# rgb.net
KiCad netlist of a schematic drawn in EAGLE
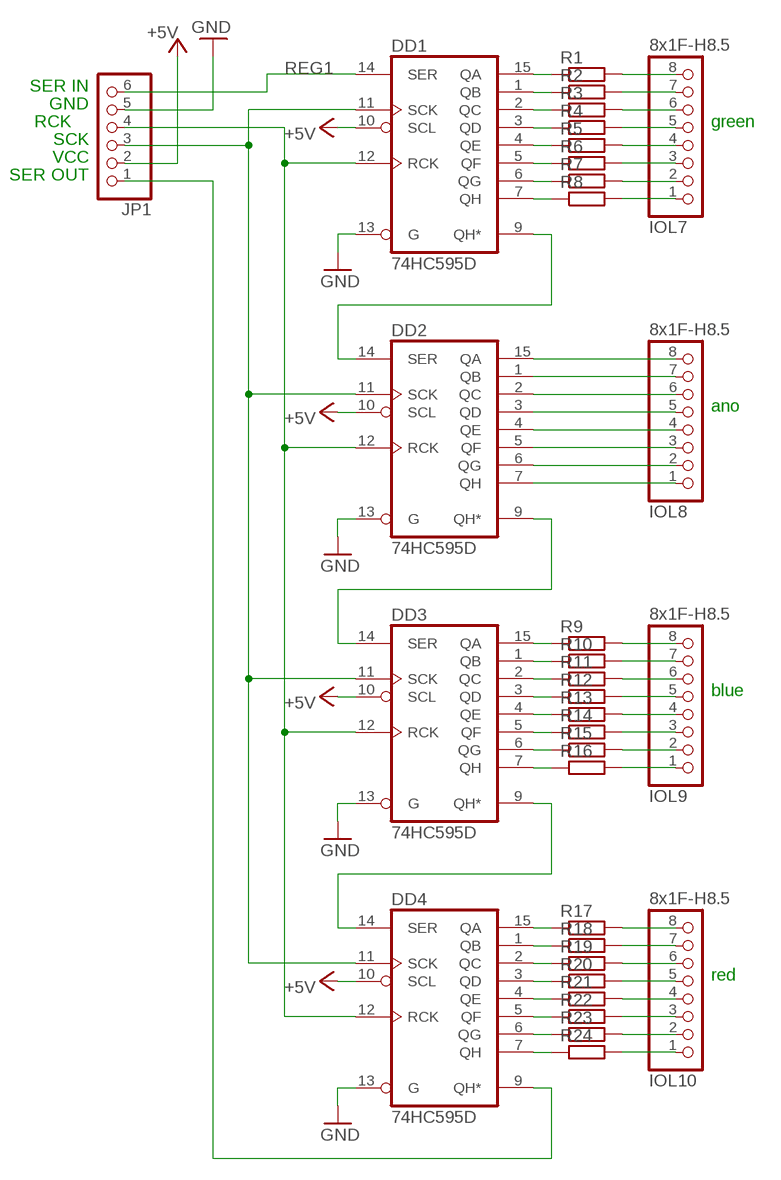
[diagram p0: schematic, sheet 1]

(export (version "E")
  (design (tool "Eeschema 10.0.6"))
  (components
    (comp (ref "DD1")
      (value "74HC595D")
      (footprint "eagle-import:SO16")
      (libsource (lib "eagle-import") (part "74595DHC"))
    )
    (comp (ref "DD2")
      (value "74HC595D")
      (footprint "eagle-import:SO16")
      (libsource (lib "eagle-import") (part "74595DHC"))
    )
    (comp (ref "DD3")
      (value "74HC595D")
      (footprint "eagle-import:SO16")
      (libsource (lib "eagle-import") (part "74595DHC"))
    )
    (comp (ref "DD4")
      (value "74HC595D")
      (footprint "eagle-import:SO16")
      (libsource (lib "eagle-import") (part "74595DHC"))
    )
    (comp (ref "IOL7")
      (value "8x1F-H8.5")
      (footprint "eagle-import:1X08")
      (libsource (lib "eagle-import") (part "PINHD-1X8"))
    )
    (comp (ref "IOL8")
      (value "8x1F-H8.5")
      (footprint "eagle-import:1X08")
      (libsource (lib "eagle-import") (part "PINHD-1X8"))
    )
    (comp (ref "IOL9")
      (value "8x1F-H8.5")
      (footprint "eagle-import:1X08")
      (libsource (lib "eagle-import") (part "PINHD-1X8"))
    )
    (comp (ref "IOL10")
      (value "8x1F-H8.5")
      (footprint "eagle-import:1X08")
      (libsource (lib "eagle-import") (part "PINHD-1X8"))
    )
    (comp (ref "JP1")
      (value "PINHD-1X6")
      (footprint "eagle-import:1X06")
      (libsource (lib "eagle-import") (part "PINHD-1X6"))
    )
    (comp (ref "R1")
      (value "R-EU_R0805")
      (footprint "eagle-import:R0805")
      (libsource (lib "eagle-import") (part "R-EU_R0805"))
    )
    (comp (ref "R2")
      (value "R-EU_R0805")
      (footprint "eagle-import:R0805")
      (libsource (lib "eagle-import") (part "R-EU_R0805"))
    )
    (comp (ref "R3")
      (value "R-EU_R0805")
      (footprint "eagle-import:R0805")
      (libsource (lib "eagle-import") (part "R-EU_R0805"))
    )
    (comp (ref "R4")
      (value "R-EU_R0805")
      (footprint "eagle-import:R0805")
      (libsource (lib "eagle-import") (part "R-EU_R0805"))
    )
    (comp (ref "R5")
      (value "R-EU_R0805")
      (footprint "eagle-import:R0805")
      (libsource (lib "eagle-import") (part "R-EU_R0805"))
    )
    (comp (ref "R6")
      (value "R-EU_R0805")
      (footprint "eagle-import:R0805")
      (libsource (lib "eagle-import") (part "R-EU_R0805"))
    )
    (comp (ref "R7")
      (value "R-EU_R0805")
      (footprint "eagle-import:R0805")
      (libsource (lib "eagle-import") (part "R-EU_R0805"))
    )
    (comp (ref "R8")
      (value "R-EU_R0805")
      (footprint "eagle-import:R0805")
      (libsource (lib "eagle-import") (part "R-EU_R0805"))
    )
    (comp (ref "R9")
      (value "R-EU_R0805")
      (footprint "eagle-import:R0805")
      (libsource (lib "eagle-import") (part "R-EU_R0805"))
    )
    (comp (ref "R10")
      (value "R-EU_R0805")
      (footprint "eagle-import:R0805")
      (libsource (lib "eagle-import") (part "R-EU_R0805"))
    )
    (comp (ref "R11")
      (value "R-EU_R0805")
      (footprint "eagle-import:R0805")
      (libsource (lib "eagle-import") (part "R-EU_R0805"))
    )
    (comp (ref "R12")
      (value "R-EU_R0805")
      (footprint "eagle-import:R0805")
      (libsource (lib "eagle-import") (part "R-EU_R0805"))
    )
    (comp (ref "R13")
      (value "R-EU_R0805")
      (footprint "eagle-import:R0805")
      (libsource (lib "eagle-import") (part "R-EU_R0805"))
    )
    (comp (ref "R14")
      (value "R-EU_R0805")
      (footprint "eagle-import:R0805")
      (libsource (lib "eagle-import") (part "R-EU_R0805"))
    )
    (comp (ref "R15")
      (value "R-EU_R0805")
      (footprint "eagle-import:R0805")
      (libsource (lib "eagle-import") (part "R-EU_R0805"))
    )
    (comp (ref "R16")
      (value "R-EU_R0805")
      (footprint "eagle-import:R0805")
      (libsource (lib "eagle-import") (part "R-EU_R0805"))
    )
    (comp (ref "R17")
      (value "R-EU_R0805")
      (footprint "eagle-import:R0805")
      (libsource (lib "eagle-import") (part "R-EU_R0805"))
    )
    (comp (ref "R18")
      (value "R-EU_R0805")
      (footprint "eagle-import:R0805")
      (libsource (lib "eagle-import") (part "R-EU_R0805"))
    )
    (comp (ref "R19")
      (value "R-EU_R0805")
      (footprint "eagle-import:R0805")
      (libsource (lib "eagle-import") (part "R-EU_R0805"))
    )
    (comp (ref "R20")
      (value "R-EU_R0805")
      (footprint "eagle-import:R0805")
      (libsource (lib "eagle-import") (part "R-EU_R0805"))
    )
    (comp (ref "R21")
      (value "R-EU_R0805")
      (footprint "eagle-import:R0805")
      (libsource (lib "eagle-import") (part "R-EU_R0805"))
    )
    (comp (ref "R22")
      (value "R-EU_R0805")
      (footprint "eagle-import:R0805")
      (libsource (lib "eagle-import") (part "R-EU_R0805"))
    )
    (comp (ref "R23")
      (value "R-EU_R0805")
      (footprint "eagle-import:R0805")
      (libsource (lib "eagle-import") (part "R-EU_R0805"))
    )
    (comp (ref "R24")
      (value "R-EU_R0805")
      (footprint "eagle-import:R0805")
      (libsource (lib "eagle-import") (part "R-EU_R0805"))
    )
  )
  (nets
    (net (code "1") (name "+5V") (class "Default")
      (node (ref "DD1") (pin "10") (pinfunction "SCL_10") (pintype "input"))
      (node (ref "DD2") (pin "10") (pinfunction "SCL_10") (pintype "input"))
      (node (ref "DD3") (pin "10") (pinfunction "SCL_10") (pintype "input"))
      (node (ref "DD4") (pin "10") (pinfunction "SCL_10") (pintype "input"))
      (node (ref "JP1") (pin "2") (pinfunction "2_2") (pintype "passive"))
    )
    (net (code "2") (name "/REG1") (class "Default")
      (node (ref "DD1") (pin "14") (pinfunction "SER_14") (pintype "input"))
      (node (ref "JP1") (pin "6") (pinfunction "6_6") (pintype "passive"))
    )
    (net (code "3") (name "GND") (class "Default")
      (node (ref "DD1") (pin "13") (pinfunction "G_13") (pintype "input"))
      (node (ref "DD2") (pin "13") (pinfunction "G_13") (pintype "input"))
      (node (ref "DD3") (pin "13") (pinfunction "G_13") (pintype "input"))
      (node (ref "DD4") (pin "13") (pinfunction "G_13") (pintype "input"))
      (node (ref "JP1") (pin "5") (pinfunction "5_5") (pintype "passive"))
    )
    (net (code "4") (name "Net-(DD1A-QA)") (class "Default")
      (node (ref "DD1") (pin "15") (pinfunction "QA_15") (pintype "tri_state"))
      (node (ref "R1") (pin "1") (pinfunction "1_1") (pintype "passive"))
    )
    (net (code "5") (name "Net-(DD1A-QB)") (class "Default")
      (node (ref "DD1") (pin "1") (pinfunction "QB_1") (pintype "tri_state"))
      (node (ref "R2") (pin "1") (pinfunction "1_1") (pintype "passive"))
    )
    (net (code "6") (name "Net-(DD1A-QC)") (class "Default")
      (node (ref "DD1") (pin "2") (pinfunction "QC_2") (pintype "tri_state"))
      (node (ref "R3") (pin "1") (pinfunction "1_1") (pintype "passive"))
    )
    (net (code "7") (name "Net-(DD1A-QD)") (class "Default")
      (node (ref "DD1") (pin "3") (pinfunction "QD_3") (pintype "tri_state"))
      (node (ref "R4") (pin "1") (pinfunction "1_1") (pintype "passive"))
    )
    (net (code "8") (name "Net-(DD1A-QE)") (class "Default")
      (node (ref "DD1") (pin "4") (pinfunction "QE_4") (pintype "tri_state"))
      (node (ref "R5") (pin "1") (pinfunction "1_1") (pintype "passive"))
    )
    (net (code "9") (name "Net-(DD1A-QF)") (class "Default")
      (node (ref "DD1") (pin "5") (pinfunction "QF_5") (pintype "tri_state"))
      (node (ref "R6") (pin "1") (pinfunction "1_1") (pintype "passive"))
    )
    (net (code "10") (name "Net-(DD1A-QG)") (class "Default")
      (node (ref "DD1") (pin "6") (pinfunction "QG_6") (pintype "tri_state"))
      (node (ref "R7") (pin "1") (pinfunction "1_1") (pintype "passive"))
    )
    (net (code "11") (name "Net-(DD1A-QH)") (class "Default")
      (node (ref "DD1") (pin "7") (pinfunction "QH_7") (pintype "tri_state"))
      (node (ref "R8") (pin "1") (pinfunction "1_1") (pintype "passive"))
    )
    (net (code "12") (name "Net-(DD1A-QH*)") (class "Default")
      (node (ref "DD1") (pin "9") (pinfunction "QH*_9") (pintype "tri_state"))
      (node (ref "DD2") (pin "14") (pinfunction "SER_14") (pintype "input"))
    )
    (net (code "13") (name "Net-(DD1A-RCK)") (class "Default")
      (node (ref "DD1") (pin "12") (pinfunction "RCK_12") (pintype "input"))
      (node (ref "DD2") (pin "12") (pinfunction "RCK_12") (pintype "input"))
      (node (ref "DD3") (pin "12") (pinfunction "RCK_12") (pintype "input"))
      (node (ref "DD4") (pin "12") (pinfunction "RCK_12") (pintype "input"))
      (node (ref "JP1") (pin "4") (pinfunction "4_4") (pintype "passive"))
    )
    (net (code "14") (name "Net-(DD1A-SCK)") (class "Default")
      (node (ref "DD1") (pin "11") (pinfunction "SCK_11") (pintype "input"))
      (node (ref "DD2") (pin "11") (pinfunction "SCK_11") (pintype "input"))
      (node (ref "DD3") (pin "11") (pinfunction "SCK_11") (pintype "input"))
      (node (ref "DD4") (pin "11") (pinfunction "SCK_11") (pintype "input"))
      (node (ref "JP1") (pin "3") (pinfunction "3_3") (pintype "passive"))
    )
    (net (code "15") (name "Net-(DD2A-QA)") (class "Default")
      (node (ref "DD2") (pin "15") (pinfunction "QA_15") (pintype "tri_state"))
      (node (ref "IOL8") (pin "8") (pinfunction "8_8") (pintype "passive"))
    )
    (net (code "16") (name "Net-(DD2A-QB)") (class "Default")
      (node (ref "DD2") (pin "1") (pinfunction "QB_1") (pintype "tri_state"))
      (node (ref "IOL8") (pin "7") (pinfunction "7_7") (pintype "passive"))
    )
    (net (code "17") (name "Net-(DD2A-QC)") (class "Default")
      (node (ref "DD2") (pin "2") (pinfunction "QC_2") (pintype "tri_state"))
      (node (ref "IOL8") (pin "6") (pinfunction "6_6") (pintype "passive"))
    )
    (net (code "18") (name "Net-(DD2A-QD)") (class "Default")
      (node (ref "DD2") (pin "3") (pinfunction "QD_3") (pintype "tri_state"))
      (node (ref "IOL8") (pin "5") (pinfunction "5_5") (pintype "passive"))
    )
    (net (code "19") (name "Net-(DD2A-QE)") (class "Default")
      (node (ref "DD2") (pin "4") (pinfunction "QE_4") (pintype "tri_state"))
      (node (ref "IOL8") (pin "4") (pinfunction "4_4") (pintype "passive"))
    )
    (net (code "20") (name "Net-(DD2A-QF)") (class "Default")
      (node (ref "DD2") (pin "5") (pinfunction "QF_5") (pintype "tri_state"))
      (node (ref "IOL8") (pin "3") (pinfunction "3_3") (pintype "passive"))
    )
    (net (code "21") (name "Net-(DD2A-QG)") (class "Default")
      (node (ref "DD2") (pin "6") (pinfunction "QG_6") (pintype "tri_state"))
      (node (ref "IOL8") (pin "2") (pinfunction "2_2") (pintype "passive"))
    )
    (net (code "22") (name "Net-(DD2A-QH)") (class "Default")
      (node (ref "DD2") (pin "7") (pinfunction "QH_7") (pintype "tri_state"))
      (node (ref "IOL8") (pin "1") (pinfunction "1_1") (pintype "passive"))
    )
    (net (code "23") (name "Net-(DD2A-QH*)") (class "Default")
      (node (ref "DD2") (pin "9") (pinfunction "QH*_9") (pintype "tri_state"))
      (node (ref "DD3") (pin "14") (pinfunction "SER_14") (pintype "input"))
    )
    (net (code "24") (name "Net-(DD3A-QA)") (class "Default")
      (node (ref "DD3") (pin "15") (pinfunction "QA_15") (pintype "tri_state"))
      (node (ref "R9") (pin "1") (pinfunction "1_1") (pintype "passive"))
    )
    (net (code "25") (name "Net-(DD3A-QB)") (class "Default")
      (node (ref "DD3") (pin "1") (pinfunction "QB_1") (pintype "tri_state"))
      (node (ref "R10") (pin "1") (pinfunction "1_1") (pintype "passive"))
    )
    (net (code "26") (name "Net-(DD3A-QC)") (class "Default")
      (node (ref "DD3") (pin "2") (pinfunction "QC_2") (pintype "tri_state"))
      (node (ref "R11") (pin "1") (pinfunction "1_1") (pintype "passive"))
    )
    (net (code "27") (name "Net-(DD3A-QD)") (class "Default")
      (node (ref "DD3") (pin "3") (pinfunction "QD_3") (pintype "tri_state"))
      (node (ref "R12") (pin "1") (pinfunction "1_1") (pintype "passive"))
    )
    (net (code "28") (name "Net-(DD3A-QE)") (class "Default")
      (node (ref "DD3") (pin "4") (pinfunction "QE_4") (pintype "tri_state"))
      (node (ref "R13") (pin "1") (pinfunction "1_1") (pintype "passive"))
    )
    (net (code "29") (name "Net-(DD3A-QF)") (class "Default")
      (node (ref "DD3") (pin "5") (pinfunction "QF_5") (pintype "tri_state"))
      (node (ref "R14") (pin "1") (pinfunction "1_1") (pintype "passive"))
    )
    (net (code "30") (name "Net-(DD3A-QG)") (class "Default")
      (node (ref "DD3") (pin "6") (pinfunction "QG_6") (pintype "tri_state"))
      (node (ref "R15") (pin "1") (pinfunction "1_1") (pintype "passive"))
    )
    (net (code "31") (name "Net-(DD3A-QH)") (class "Default")
      (node (ref "DD3") (pin "7") (pinfunction "QH_7") (pintype "tri_state"))
      (node (ref "R16") (pin "1") (pinfunction "1_1") (pintype "passive"))
    )
    (net (code "32") (name "Net-(DD3A-QH*)") (class "Default")
      (node (ref "DD3") (pin "9") (pinfunction "QH*_9") (pintype "tri_state"))
      (node (ref "DD4") (pin "14") (pinfunction "SER_14") (pintype "input"))
    )
    (net (code "33") (name "Net-(DD4A-QA)") (class "Default")
      (node (ref "DD4") (pin "15") (pinfunction "QA_15") (pintype "tri_state"))
      (node (ref "R17") (pin "1") (pinfunction "1_1") (pintype "passive"))
    )
    (net (code "34") (name "Net-(DD4A-QB)") (class "Default")
      (node (ref "DD4") (pin "1") (pinfunction "QB_1") (pintype "tri_state"))
      (node (ref "R18") (pin "1") (pinfunction "1_1") (pintype "passive"))
    )
    (net (code "35") (name "Net-(DD4A-QC)") (class "Default")
      (node (ref "DD4") (pin "2") (pinfunction "QC_2") (pintype "tri_state"))
      (node (ref "R19") (pin "1") (pinfunction "1_1") (pintype "passive"))
    )
    (net (code "36") (name "Net-(DD4A-QD)") (class "Default")
      (node (ref "DD4") (pin "3") (pinfunction "QD_3") (pintype "tri_state"))
      (node (ref "R20") (pin "1") (pinfunction "1_1") (pintype "passive"))
    )
    (net (code "37") (name "Net-(DD4A-QE)") (class "Default")
      (node (ref "DD4") (pin "4") (pinfunction "QE_4") (pintype "tri_state"))
      (node (ref "R21") (pin "1") (pinfunction "1_1") (pintype "passive"))
    )
    (net (code "38") (name "Net-(DD4A-QF)") (class "Default")
      (node (ref "DD4") (pin "5") (pinfunction "QF_5") (pintype "tri_state"))
      (node (ref "R22") (pin "1") (pinfunction "1_1") (pintype "passive"))
    )
    (net (code "39") (name "Net-(DD4A-QG)") (class "Default")
      (node (ref "DD4") (pin "6") (pinfunction "QG_6") (pintype "tri_state"))
      (node (ref "R23") (pin "1") (pinfunction "1_1") (pintype "passive"))
    )
    (net (code "40") (name "Net-(DD4A-QH)") (class "Default")
      (node (ref "DD4") (pin "7") (pinfunction "QH_7") (pintype "tri_state"))
      (node (ref "R24") (pin "1") (pinfunction "1_1") (pintype "passive"))
    )
    (net (code "41") (name "Net-(DD4A-QH*)") (class "Default")
      (node (ref "DD4") (pin "9") (pinfunction "QH*_9") (pintype "tri_state"))
      (node (ref "JP1") (pin "1") (pinfunction "1_1") (pintype "passive"))
    )
    (net (code "42") (name "Net-(IOL7-Pad1)") (class "Default")
      (node (ref "IOL7") (pin "1") (pinfunction "1_1") (pintype "passive"))
      (node (ref "R8") (pin "2") (pinfunction "2_2") (pintype "passive"))
    )
    (net (code "43") (name "Net-(IOL7-Pad2)") (class "Default")
      (node (ref "IOL7") (pin "2") (pinfunction "2_2") (pintype "passive"))
      (node (ref "R7") (pin "2") (pinfunction "2_2") (pintype "passive"))
    )
    (net (code "44") (name "Net-(IOL7-Pad3)") (class "Default")
      (node (ref "IOL7") (pin "3") (pinfunction "3_3") (pintype "passive"))
      (node (ref "R6") (pin "2") (pinfunction "2_2") (pintype "passive"))
    )
    (net (code "45") (name "Net-(IOL7-Pad4)") (class "Default")
      (node (ref "IOL7") (pin "4") (pinfunction "4_4") (pintype "passive"))
      (node (ref "R5") (pin "2") (pinfunction "2_2") (pintype "passive"))
    )
    (net (code "46") (name "Net-(IOL7-Pad5)") (class "Default")
      (node (ref "IOL7") (pin "5") (pinfunction "5_5") (pintype "passive"))
      (node (ref "R4") (pin "2") (pinfunction "2_2") (pintype "passive"))
    )
    (net (code "47") (name "Net-(IOL7-Pad6)") (class "Default")
      (node (ref "IOL7") (pin "6") (pinfunction "6_6") (pintype "passive"))
      (node (ref "R3") (pin "2") (pinfunction "2_2") (pintype "passive"))
    )
    (net (code "48") (name "Net-(IOL7-Pad7)") (class "Default")
      (node (ref "IOL7") (pin "7") (pinfunction "7_7") (pintype "passive"))
      (node (ref "R2") (pin "2") (pinfunction "2_2") (pintype "passive"))
    )
    (net (code "49") (name "Net-(IOL7-Pad8)") (class "Default")
      (node (ref "IOL7") (pin "8") (pinfunction "8_8") (pintype "passive"))
      (node (ref "R1") (pin "2") (pinfunction "2_2") (pintype "passive"))
    )
    (net (code "50") (name "Net-(IOL9-Pad1)") (class "Default")
      (node (ref "IOL9") (pin "1") (pinfunction "1_1") (pintype "passive"))
      (node (ref "R16") (pin "2") (pinfunction "2_2") (pintype "passive"))
    )
    (net (code "51") (name "Net-(IOL9-Pad2)") (class "Default")
      (node (ref "IOL9") (pin "2") (pinfunction "2_2") (pintype "passive"))
      (node (ref "R15") (pin "2") (pinfunction "2_2") (pintype "passive"))
    )
    (net (code "52") (name "Net-(IOL9-Pad3)") (class "Default")
      (node (ref "IOL9") (pin "3") (pinfunction "3_3") (pintype "passive"))
      (node (ref "R14") (pin "2") (pinfunction "2_2") (pintype "passive"))
    )
    (net (code "53") (name "Net-(IOL9-Pad4)") (class "Default")
      (node (ref "IOL9") (pin "4") (pinfunction "4_4") (pintype "passive"))
      (node (ref "R13") (pin "2") (pinfunction "2_2") (pintype "passive"))
    )
    (net (code "54") (name "Net-(IOL9-Pad5)") (class "Default")
      (node (ref "IOL9") (pin "5") (pinfunction "5_5") (pintype "passive"))
      (node (ref "R12") (pin "2") (pinfunction "2_2") (pintype "passive"))
    )
    (net (code "55") (name "Net-(IOL9-Pad6)") (class "Default")
      (node (ref "IOL9") (pin "6") (pinfunction "6_6") (pintype "passive"))
      (node (ref "R11") (pin "2") (pinfunction "2_2") (pintype "passive"))
    )
    (net (code "56") (name "Net-(IOL9-Pad7)") (class "Default")
      (node (ref "IOL9") (pin "7") (pinfunction "7_7") (pintype "passive"))
      (node (ref "R10") (pin "2") (pinfunction "2_2") (pintype "passive"))
    )
    (net (code "57") (name "Net-(IOL9-Pad8)") (class "Default")
      (node (ref "IOL9") (pin "8") (pinfunction "8_8") (pintype "passive"))
      (node (ref "R9") (pin "2") (pinfunction "2_2") (pintype "passive"))
    )
    (net (code "58") (name "Net-(IOL10-Pad1)") (class "Default")
      (node (ref "IOL10") (pin "1") (pinfunction "1_1") (pintype "passive"))
      (node (ref "R24") (pin "2") (pinfunction "2_2") (pintype "passive"))
    )
    (net (code "59") (name "Net-(IOL10-Pad2)") (class "Default")
      (node (ref "IOL10") (pin "2") (pinfunction "2_2") (pintype "passive"))
      (node (ref "R23") (pin "2") (pinfunction "2_2") (pintype "passive"))
    )
    (net (code "60") (name "Net-(IOL10-Pad3)") (class "Default")
      (node (ref "IOL10") (pin "3") (pinfunction "3_3") (pintype "passive"))
      (node (ref "R22") (pin "2") (pinfunction "2_2") (pintype "passive"))
    )
    (net (code "61") (name "Net-(IOL10-Pad4)") (class "Default")
      (node (ref "IOL10") (pin "4") (pinfunction "4_4") (pintype "passive"))
      (node (ref "R21") (pin "2") (pinfunction "2_2") (pintype "passive"))
    )
    (net (code "62") (name "Net-(IOL10-Pad5)") (class "Default")
      (node (ref "IOL10") (pin "5") (pinfunction "5_5") (pintype "passive"))
      (node (ref "R20") (pin "2") (pinfunction "2_2") (pintype "passive"))
    )
    (net (code "63") (name "Net-(IOL10-Pad6)") (class "Default")
      (node (ref "IOL10") (pin "6") (pinfunction "6_6") (pintype "passive"))
      (node (ref "R19") (pin "2") (pinfunction "2_2") (pintype "passive"))
    )
    (net (code "64") (name "Net-(IOL10-Pad7)") (class "Default")
      (node (ref "IOL10") (pin "7") (pinfunction "7_7") (pintype "passive"))
      (node (ref "R18") (pin "2") (pinfunction "2_2") (pintype "passive"))
    )
    (net (code "65") (name "Net-(IOL10-Pad8)") (class "Default")
      (node (ref "IOL10") (pin "8") (pinfunction "8_8") (pintype "passive"))
      (node (ref "R17") (pin "2") (pinfunction "2_2") (pintype "passive"))
    )
  )
)
